# Shoot.net
KiCad netlist of a schematic drawn in Altium Designer
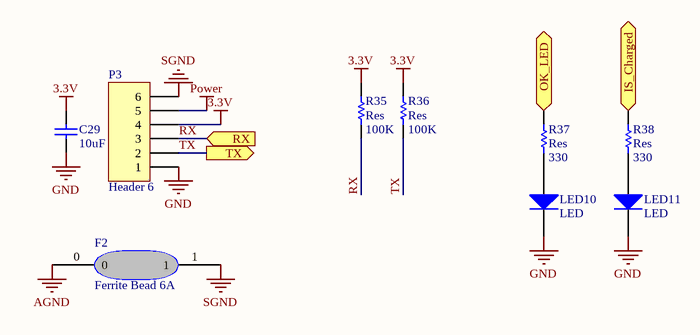
[diagram p0: Shoot.SchDoc]

(export (version "E")
  (design (tool "Eeschema 10.0.6"))
  (components
    (comp (ref "C29")
      (value "10uF")
      (footprint "2012[0805]")
      (description "Capacitor")
      (fields (field (name "Comment") "Cap_UP") (field (name "PUBLISHER") "Altium Limited"))
      (libsource (lib "KN2CLib") (part "Cap_UP"))
    )
    (comp (ref "F2")
      (value "Ferrite Bead 6A")
      (footprint "f6A")
      (libsource (lib "Ferrite Bead") (part "F6A"))
    )
    (comp (ref "LED10")
      (value "LED")
      (footprint "2012[0805]")
      (description "1 Amp General Purpose Rectifier")
      (fields (field (name "PUBLISHER") "Altium Limited"))
      (libsource (lib "KN2CLib") (part "Diode"))
    )
    (comp (ref "LED11")
      (value "LED")
      (footprint "2012[0805]")
      (description "1 Amp General Purpose Rectifier")
      (fields (field (name "PUBLISHER") "Altium Limited"))
      (libsource (lib "KN2CLib") (part "Diode"))
    )
    (comp (ref "P3")
      (value "Header 6")
      (footprint "HDR1X6")
      (description "Header, 6-Pin")
      (fields (field (name "PUBLISHER") "Altium Limited"))
      (libsource (lib "Miscellaneous Connectors") (part "Header 6"))
    )
    (comp (ref "R35")
      (value "Res")
      (footprint "2012[0805]")
      (description "Semiconductor Resistor")
      (fields (field (name "ALTIUM_VALUE") "100K") (field (name "PUBLISHER") "Altium Limited"))
      (libsource (lib "KN2CLib") (part "Res"))
    )
    (comp (ref "R36")
      (value "Res")
      (footprint "2012[0805]")
      (description "Semiconductor Resistor")
      (fields (field (name "ALTIUM_VALUE") "100K") (field (name "PUBLISHER") "Altium Limited"))
      (libsource (lib "KN2CLib") (part "Res"))
    )
    (comp (ref "R37")
      (value "Res")
      (footprint "2012[0805]")
      (description "Semiconductor Resistor")
      (fields (field (name "ALTIUM_VALUE") "330") (field (name "PUBLISHER") "Altium Limited"))
      (libsource (lib "KN2CLib") (part "Res"))
    )
    (comp (ref "R38")
      (value "Res")
      (footprint "2012[0805]")
      (description "Semiconductor Resistor")
      (fields (field (name "ALTIUM_VALUE") "330") (field (name "PUBLISHER") "Altium Limited"))
      (libsource (lib "KN2CLib") (part "Res"))
    )
  )
  (nets
    (net (code "1") (name "/IS_Charged") (class "Default")
      (node (ref "R38") (pin "1") (pinfunction "1_1") (pintype "passive"))
    )
    (net (code "2") (name "/OK_LED") (class "Default")
      (node (ref "R37") (pin "1") (pinfunction "1_1") (pintype "passive"))
    )
    (net (code "3") (name "/RX") (class "Default")
      (node (ref "P3") (pin "3") (pinfunction "3_3") (pintype "passive"))
      (node (ref "R35") (pin "1") (pinfunction "1_1") (pintype "passive"))
    )
    (net (code "4") (name "/TX") (class "Default")
      (node (ref "P3") (pin "2") (pinfunction "2_2") (pintype "passive"))
      (node (ref "R36") (pin "1") (pinfunction "1_1") (pintype "passive"))
    )
    (net (code "5") (name "3.3V") (class "Default")
      (node (ref "C29") (pin "2") (pinfunction "2_2") (pintype "passive"))
      (node (ref "P3") (pin "4") (pinfunction "4_4") (pintype "passive"))
      (node (ref "R35") (pin "2") (pinfunction "2_2") (pintype "passive"))
      (node (ref "R36") (pin "2") (pinfunction "2_2") (pintype "passive"))
    )
    (net (code "6") (name "AGND") (class "Default")
      (node (ref "F2") (pin "0") (pinfunction "0_0") (pintype "passive"))
    )
    (net (code "7") (name "GND") (class "Default")
      (node (ref "C29") (pin "1") (pinfunction "1_1") (pintype "passive"))
      (node (ref "LED10") (pin "2") (pinfunction "K_2") (pintype "passive"))
      (node (ref "LED11") (pin "2") (pinfunction "K_2") (pintype "passive"))
      (node (ref "P3") (pin "1") (pinfunction "1_1") (pintype "passive"))
    )
    (net (code "8") (name "Net-(LED10-A)") (class "Default")
      (node (ref "LED10") (pin "1") (pinfunction "A_1") (pintype "passive"))
      (node (ref "R37") (pin "2") (pinfunction "2_2") (pintype "passive"))
    )
    (net (code "9") (name "Net-(LED11-A)") (class "Default")
      (node (ref "LED11") (pin "1") (pinfunction "A_1") (pintype "passive"))
      (node (ref "R38") (pin "2") (pinfunction "2_2") (pintype "passive"))
    )
    (net (code "10") (name "Power") (class "Default")
      (node (ref "P3") (pin "5") (pinfunction "5_5") (pintype "passive"))
    )
    (net (code "11") (name "SGND") (class "Default")
      (node (ref "F2") (pin "1") (pinfunction "1_1") (pintype "passive"))
      (node (ref "P3") (pin "6") (pinfunction "6_6") (pintype "passive"))
    )
  )
)
